# L-D5019-05-02.net
KiCad netlist of a schematic drawn in Altium Designer
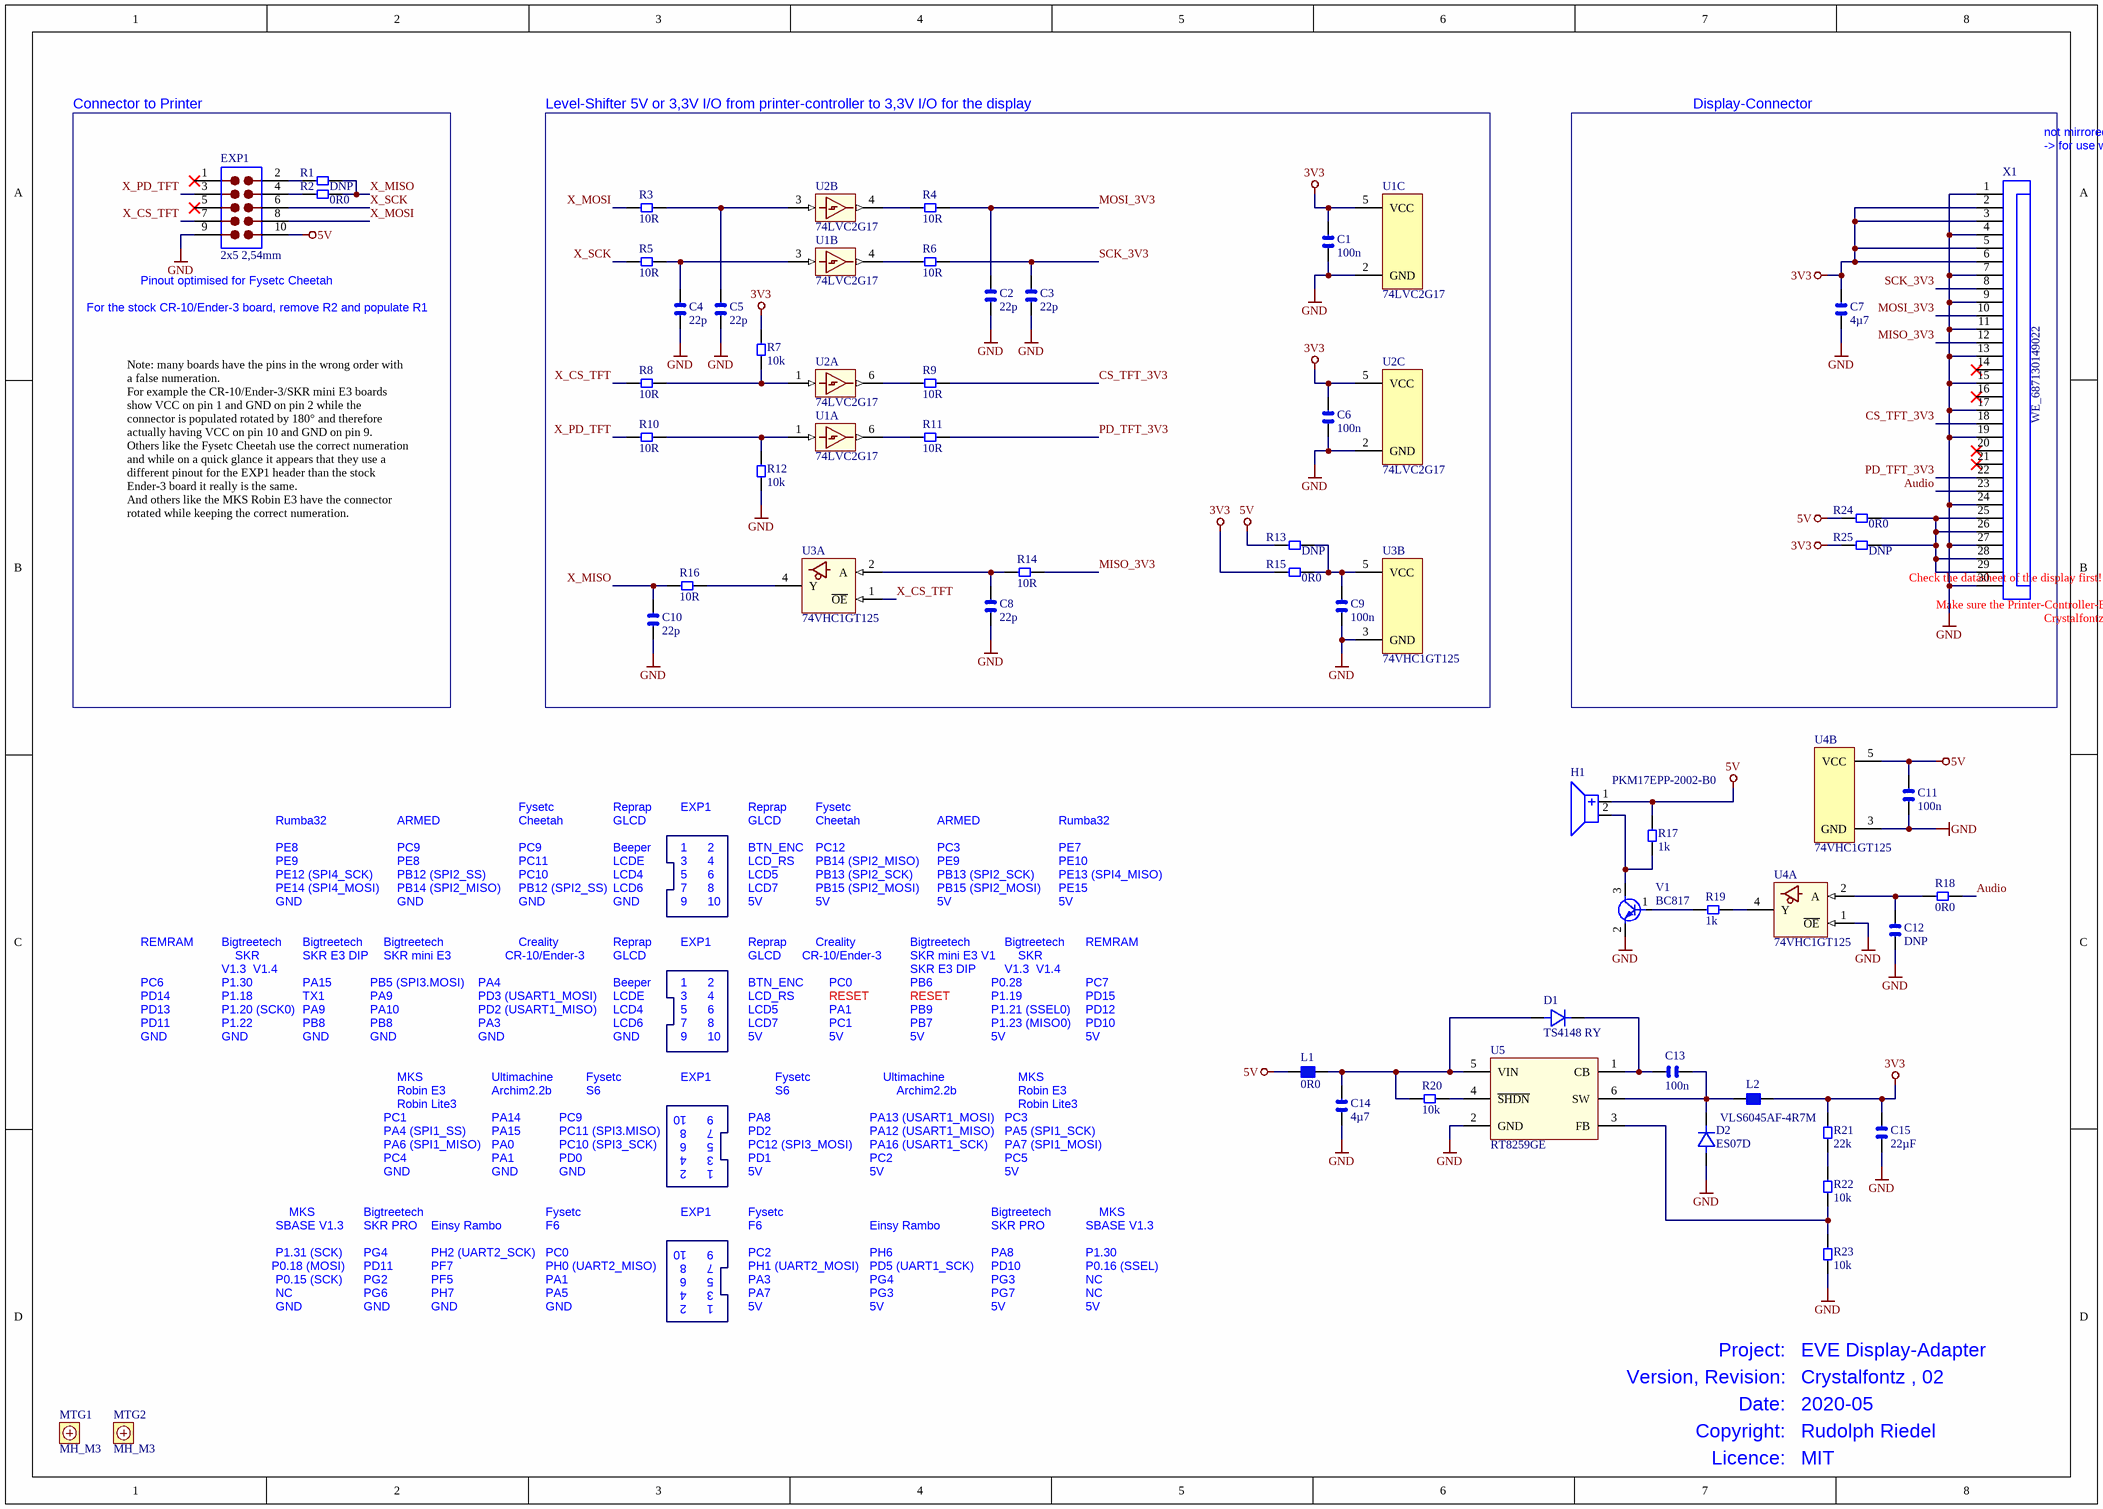
[diagram p0: L-D5019-05-02.SchDoc]

(export (version "E")
  (design (tool "Eeschema 10.0.6"))
  (components
    (comp (ref "C1")
      (value "100n")
      (footprint "CAPC2012X14L")
      (description "0805 Chip Capacitor")
      (fields (field (name "PART NUMBER") "CAPC_0805") (field (name "EDITOR") "rriedel"))
      (libsource (lib "HW-Labor_GF") (part "CAP_2_V2"))
    )
    (comp (ref "C2")
      (value "22p")
      (footprint "CAPC2012X14L")
      (description "0805 Chip Capacitor")
      (fields (field (name "PART NUMBER") "CAPC_0805") (field (name "EDITOR") "rriedel"))
      (libsource (lib "HW-Labor_GF") (part "CAP_2_V2"))
    )
    (comp (ref "C3")
      (value "22p")
      (footprint "CAPC2012X14L")
      (description "0805 Chip Capacitor")
      (fields (field (name "PART NUMBER") "CAPC_0805") (field (name "EDITOR") "rriedel"))
      (libsource (lib "HW-Labor_GF") (part "CAP_2_V2"))
    )
    (comp (ref "C4")
      (value "22p")
      (footprint "CAPC2012X14L")
      (description "0805 Chip Capacitor")
      (fields (field (name "PART NUMBER") "CAPC_0805") (field (name "EDITOR") "rriedel"))
      (libsource (lib "HW-Labor_GF") (part "CAP_2_V2"))
    )
    (comp (ref "C5")
      (value "22p")
      (footprint "CAPC2012X14L")
      (description "0805 Chip Capacitor")
      (fields (field (name "PART NUMBER") "CAPC_0805") (field (name "EDITOR") "rriedel"))
      (libsource (lib "HW-Labor_GF") (part "CAP_2_V2"))
    )
    (comp (ref "C6")
      (value "100n")
      (footprint "CAPC2012X14L")
      (description "0805 Chip Capacitor")
      (fields (field (name "PART NUMBER") "CAPC_0805") (field (name "EDITOR") "rriedel"))
      (libsource (lib "HW-Labor_GF") (part "CAP_2_V2"))
    )
    (comp (ref "C7")
      (value "4µ7")
      (footprint "CAPC2012X14L")
      (description "0805 Chip Capacitor")
      (fields (field (name "PART NUMBER") "CAPC_0805") (field (name "EDITOR") "rriedel"))
      (libsource (lib "HW-Labor_GF") (part "CAP_2_V2"))
    )
    (comp (ref "C8")
      (value "22p")
      (footprint "CAPC2012X14L")
      (description "0805 Chip Capacitor")
      (fields (field (name "PART NUMBER") "CAPC_0805") (field (name "EDITOR") "rriedel"))
      (libsource (lib "HW-Labor_GF") (part "CAP_2_V2"))
    )
    (comp (ref "C9")
      (value "100n")
      (footprint "CAPC2012X14L")
      (description "0805 Chip Capacitor")
      (fields (field (name "PART NUMBER") "CAPC_0805") (field (name "EDITOR") "rriedel"))
      (libsource (lib "HW-Labor_GF") (part "CAP_2_V2"))
    )
    (comp (ref "C10")
      (value "22p")
      (footprint "CAPC2012X14L")
      (description "0805 Chip Capacitor")
      (fields (field (name "PART NUMBER") "CAPC_0805") (field (name "EDITOR") "rriedel"))
      (libsource (lib "HW-Labor_GF") (part "CAP_2_V2"))
    )
    (comp (ref "C11")
      (value "100n")
      (footprint "CAPC2012X14L")
      (description "0805 Chip Capacitor")
      (fields (field (name "PART NUMBER") "CAPC_0805") (field (name "EDITOR") "rriedel"))
      (libsource (lib "HW-Labor_GF") (part "CAP_2_V2"))
    )
    (comp (ref "C12")
      (value "DNP")
      (footprint "CAPC2012X14L")
      (description "0805 Chip Capacitor")
      (fields (field (name "PART NUMBER") "CAPC_0805") (field (name "EDITOR") "rriedel"))
      (libsource (lib "HW-Labor_GF") (part "CAP_2_V2"))
    )
    (comp (ref "C13")
      (value "100n")
      (footprint "CAPC2012X14L")
      (description "0805 Chip Capacitor")
      (fields (field (name "PART NUMBER") "CAPC_0805") (field (name "EDITOR") "rriedel"))
      (libsource (lib "HW-Labor_GF") (part "CAP_2_V2"))
    )
    (comp (ref "C14")
      (value "4µ7")
      (footprint "CAPC2012X14L")
      (description "0805 Chip Capacitor")
      (fields (field (name "PART NUMBER") "CAPC_0805") (field (name "EDITOR") "rriedel"))
      (libsource (lib "HW-Labor_GF") (part "CAP_2_V2"))
    )
    (comp (ref "C15")
      (value "22µF")
      (footprint "CAPC3216X19N")
      (description "1206 Chip Capacitor")
      (fields (field (name "PART NUMBER") "CAPC_1206") (field (name "EDITOR") "rriedel"))
      (libsource (lib "HW-Labor_GF") (part "CAP_2_V2"))
    )
    (comp (ref "D1")
      (value "TS4148 RY")
      (footprint "DIOC2012X10N")
      (description "Small Signal Diode IF 0.3A, VR 75V, 0805")
      (fields
        (field (name "PART NUMBER") "TSC_TS4148 RY")
        (field (name "MANUFACTURER") "TSC")
        (field (name "EDITOR") "rriedel")
      )
      (libsource (lib "HW-Labor_GF") (part "Diode_A2_K1"))
    )
    (comp (ref "D2")
      (value "ES07D")
      (footprint "DIOM2818X11N")
      (description "Ultrafast Rectifier Surface Mount,  IF 0.5A, VR 100V, DO-219AB, AEC-Q101")
      (fields (field (name "MANUFACTURER") "Vishay") (field (name "EDITOR") "rriedel"))
      (libsource (lib "HW-Labor_GF") (part "Diode_A2_K1"))
    )
    (comp (ref "EXP1")
      (value "2x5 2,54mm")
      (footprint "PINH_2x5_2_54mm_shroud")
      (description "Pin-Header 2,54 mm 2x5pins, shrouded")
      (fields (field (name "PART NUMBER") "PINH_2x5_2_54") (field (name "EDITOR") "rriedel"))
      (libsource (lib "HW-Labor_GF") (part "CONM_2x5_V2"))
    )
    (comp (ref "H1")
      (value "PKM17EPP-2002-B0")
      (footprint "Speaker_17mm")
      (description "Speaker, Piezo, THT, dia 17mm,  height 8.6 mm")
      (fields
        (field (name "MANUFACTURER") "Murata")
        (field (name "DISTRIBUTOR_1_PART_NUMBER") "490-4688-ND")
        (field (name "EDITOR") "rriedel")
      )
      (libsource (lib "HW-Labor_GF") (part "Speaker"))
    )
    (comp (ref "L1")
      (value "0R0")
      (footprint "INDC2012X10L")
      (description "0805 Chip Inductor")
      (fields (field (name "PART NUMBER") "INDC_0805") (field (name "EDITOR") "rriedel"))
      (libsource (lib "HW-Labor_GF") (part "IND_2_V1"))
    )
    (comp (ref "L2")
      (value "VLS6045AF-4R7M")
      (footprint "PowerInductor_6x6")
      (description "4,7µH, shielded, 4,7A, 26mR")
      (fields
        (field (name "MANUFACTURER") "TDK")
        (field (name "DISTRIBUTOR_1_PART_NUMBER") "445-180835-1-ND")
        (field (name "EDITOR") "rriedel")
      )
      (libsource (lib "HW-Labor_GF") (part "IND_2_V1"))
    )
    (comp (ref "MTG1")
      (value "MH_M3")
      (footprint "HOLE_3_2MM")
      (description "Mounting-Hole for M3 screws")
      (fields (field (name "EDITOR") "rriedel"))
      (libsource (lib "HW-Labor_GF") (part "MTG_V1"))
    )
    (comp (ref "MTG2")
      (value "MH_M3")
      (footprint "HOLE_3_2MM")
      (description "Mounting-Hole for M3 screws")
      (fields (field (name "EDITOR") "rriedel"))
      (libsource (lib "HW-Labor_GF") (part "MTG_V1"))
    )
    (comp (ref "R1")
      (value "DNP")
      (footprint "RESC2012X06L")
      (description "0805 Chip Resistor")
      (fields (field (name "PART NUMBER") "RESC_0805") (field (name "EDITOR") "rriedel"))
      (libsource (lib "HW-Labor_GF") (part "RES_2_V2"))
    )
    (comp (ref "R2")
      (value "0R0")
      (footprint "RESC2012X06L")
      (description "0805 Chip Resistor")
      (fields (field (name "PART NUMBER") "RESC_0805") (field (name "EDITOR") "rriedel"))
      (libsource (lib "HW-Labor_GF") (part "RES_2_V2"))
    )
    (comp (ref "R3")
      (value "10R")
      (footprint "RESC2012X06L")
      (description "0805 Chip Resistor")
      (fields (field (name "PART NUMBER") "RESC_0805") (field (name "EDITOR") "rriedel"))
      (libsource (lib "HW-Labor_GF") (part "RES_2_V2"))
    )
    (comp (ref "R4")
      (value "10R")
      (footprint "RESC2012X06L")
      (description "0805 Chip Resistor")
      (fields (field (name "PART NUMBER") "RESC_0805") (field (name "EDITOR") "rriedel"))
      (libsource (lib "HW-Labor_GF") (part "RES_2_V2"))
    )
    (comp (ref "R5")
      (value "10R")
      (footprint "RESC2012X06L")
      (description "0805 Chip Resistor")
      (fields (field (name "PART NUMBER") "RESC_0805") (field (name "EDITOR") "rriedel"))
      (libsource (lib "HW-Labor_GF") (part "RES_2_V2"))
    )
    (comp (ref "R6")
      (value "10R")
      (footprint "RESC2012X06L")
      (description "0805 Chip Resistor")
      (fields (field (name "PART NUMBER") "RESC_0805") (field (name "EDITOR") "rriedel"))
      (libsource (lib "HW-Labor_GF") (part "RES_2_V2"))
    )
    (comp (ref "R7")
      (value "10k")
      (footprint "RESC2012X06L")
      (description "0805 Chip Resistor")
      (fields (field (name "PART NUMBER") "RESC_0805") (field (name "EDITOR") "rriedel"))
      (libsource (lib "HW-Labor_GF") (part "RES_2_V2"))
    )
    (comp (ref "R8")
      (value "10R")
      (footprint "RESC2012X06L")
      (description "0805 Chip Resistor")
      (fields (field (name "PART NUMBER") "RESC_0805") (field (name "EDITOR") "rriedel"))
      (libsource (lib "HW-Labor_GF") (part "RES_2_V2"))
    )
    (comp (ref "R9")
      (value "10R")
      (footprint "RESC2012X06L")
      (description "0805 Chip Resistor")
      (fields (field (name "PART NUMBER") "RESC_0805") (field (name "EDITOR") "rriedel"))
      (libsource (lib "HW-Labor_GF") (part "RES_2_V2"))
    )
    (comp (ref "R10")
      (value "10R")
      (footprint "RESC2012X06L")
      (description "0805 Chip Resistor")
      (fields (field (name "PART NUMBER") "RESC_0805") (field (name "EDITOR") "rriedel"))
      (libsource (lib "HW-Labor_GF") (part "RES_2_V2"))
    )
    (comp (ref "R11")
      (value "10R")
      (footprint "RESC2012X06L")
      (description "0805 Chip Resistor")
      (fields (field (name "PART NUMBER") "RESC_0805") (field (name "EDITOR") "rriedel"))
      (libsource (lib "HW-Labor_GF") (part "RES_2_V2"))
    )
    (comp (ref "R12")
      (value "10k")
      (footprint "RESC2012X06L")
      (description "0805 Chip Resistor")
      (fields (field (name "PART NUMBER") "RESC_0805") (field (name "EDITOR") "rriedel"))
      (libsource (lib "HW-Labor_GF") (part "RES_2_V2"))
    )
    (comp (ref "R13")
      (value "DNP")
      (footprint "RESC2012X06L")
      (description "0805 Chip Resistor")
      (fields (field (name "PART NUMBER") "RESC_0805") (field (name "EDITOR") "rriedel"))
      (libsource (lib "HW-Labor_GF") (part "RES_2_V2"))
    )
    (comp (ref "R14")
      (value "10R")
      (footprint "RESC2012X06L")
      (description "0805 Chip Resistor")
      (fields (field (name "PART NUMBER") "RESC_0805") (field (name "EDITOR") "rriedel"))
      (libsource (lib "HW-Labor_GF") (part "RES_2_V2"))
    )
    (comp (ref "R15")
      (value "0R0")
      (footprint "RESC2012X06L")
      (description "0805 Chip Resistor")
      (fields (field (name "PART NUMBER") "RESC_0805") (field (name "EDITOR") "rriedel"))
      (libsource (lib "HW-Labor_GF") (part "RES_2_V2"))
    )
    (comp (ref "R16")
      (value "10R")
      (footprint "RESC2012X06L")
      (description "0805 Chip Resistor")
      (fields (field (name "PART NUMBER") "RESC_0805") (field (name "EDITOR") "rriedel"))
      (libsource (lib "HW-Labor_GF") (part "RES_2_V2"))
    )
    (comp (ref "R17")
      (value "1k")
      (footprint "RESC2012X06L")
      (description "0805 Chip Resistor")
      (fields (field (name "PART NUMBER") "RESC_0805") (field (name "EDITOR") "rriedel"))
      (libsource (lib "HW-Labor_GF") (part "RES_2_V2"))
    )
    (comp (ref "R18")
      (value "0R0")
      (footprint "RESC2012X06L")
      (description "0805 Chip Resistor")
      (fields (field (name "PART NUMBER") "RESC_0805") (field (name "EDITOR") "rriedel"))
      (libsource (lib "HW-Labor_GF") (part "RES_2_V2"))
    )
    (comp (ref "R19")
      (value "1k")
      (footprint "RESC2012X06L")
      (description "0805 Chip Resistor")
      (fields (field (name "PART NUMBER") "RESC_0805") (field (name "EDITOR") "rriedel"))
      (libsource (lib "HW-Labor_GF") (part "RES_2_V2"))
    )
    (comp (ref "R20")
      (value "10k")
      (footprint "RESC2012X06L")
      (description "0805 Chip Resistor")
      (fields (field (name "PART NUMBER") "RESC_0805") (field (name "EDITOR") "rriedel"))
      (libsource (lib "HW-Labor_GF") (part "RES_2_V2"))
    )
    (comp (ref "R21")
      (value "22k")
      (footprint "RESC2012X06L")
      (description "0805 Chip Resistor")
      (fields (field (name "PART NUMBER") "RESC_0805") (field (name "EDITOR") "rriedel"))
      (libsource (lib "HW-Labor_GF") (part "RES_2_V2"))
    )
    (comp (ref "R22")
      (value "10k")
      (footprint "RESC2012X06L")
      (description "0805 Chip Resistor")
      (fields (field (name "PART NUMBER") "RESC_0805") (field (name "EDITOR") "rriedel"))
      (libsource (lib "HW-Labor_GF") (part "RES_2_V2"))
    )
    (comp (ref "R23")
      (value "10k")
      (footprint "RESC2012X06L")
      (description "0805 Chip Resistor")
      (fields (field (name "PART NUMBER") "RESC_0805") (field (name "EDITOR") "rriedel"))
      (libsource (lib "HW-Labor_GF") (part "RES_2_V2"))
    )
    (comp (ref "R24")
      (value "0R0")
      (footprint "RESC2012X06L")
      (description "0805 Chip Resistor")
      (fields (field (name "PART NUMBER") "RESC_0805") (field (name "EDITOR") "rriedel"))
      (libsource (lib "HW-Labor_GF") (part "RES_2_V2"))
    )
    (comp (ref "R25")
      (value "DNP")
      (footprint "RESC2012X06L")
      (description "0805 Chip Resistor")
      (fields (field (name "PART NUMBER") "RESC_0805") (field (name "EDITOR") "rriedel"))
      (libsource (lib "HW-Labor_GF") (part "RES_2_V2"))
    )
    (comp (ref "U1")
      (value "74LVC2G17")
      (footprint "SOT95P280X110-6N")
      (description "Dual Schmitt-Trigger Buffer with 5.5V tolerant inputs")
      (fields
        (field (name "MANUFACTURER") "TI")
        (field (name "DISTRIBUTOR_1_PART_NUMBER") "296-SN74LVC2G17DBVRCT-ND‎")
        (field (name "EDITOR") "rriedel")
      )
      (libsource (lib "HW-Labor_GF") (part "74LVC2G17"))
    )
    (comp (ref "U2")
      (value "74LVC2G17")
      (footprint "SOT95P280X110-6N")
      (description "Dual Schmitt-Trigger Buffer with 5.5V tolerant inputs")
      (fields
        (field (name "MANUFACTURER") "TI")
        (field (name "DISTRIBUTOR_1_PART_NUMBER") "296-SN74LVC2G17DBVRCT-ND‎")
        (field (name "EDITOR") "rriedel")
      )
      (libsource (lib "HW-Labor_GF") (part "74LVC2G17"))
    )
    (comp (ref "U3")
      (value "74VHC1GT125")
      (footprint "SOT95P280X110-5N")
      (description "1x Buffer with OE; 3-state,Level Shifter 3,3V to 5V and 5V to 3.3V")
      (fields
        (field (name "MANUFACTURER") "ON Semiconductor")
        (field (name "DISTRIBUTOR_1_PART_NUMBER") "1703291")
        (field (name "EDITOR") "rriedel")
      )
      (libsource (lib "") (part "74LVC1G125G_1"))
    )
    (comp (ref "U4")
      (value "74VHC1GT125")
      (footprint "SOT95P280X110-5N")
      (description "1x Buffer with OE; 3-state,Level Shifter 3,3V to 5V and 5V to 3.3V")
      (fields
        (field (name "MANUFACTURER") "ON Semiconductor")
        (field (name "DISTRIBUTOR_1_PART_NUMBER") "1703291")
        (field (name "EDITOR") "rriedel")
      )
      (libsource (lib "HW-Labor_GF") (part "74LVC1G125G"))
    )
    (comp (ref "U5")
      (value "RT8259GE")
      (footprint "SOT95P280X110-6N")
      (description "Step-Down DC/DC Regulator, 24V, 1.2A, 1,4MHz")
      (fields
        (field (name "MANUFACTURER") "Richtek")
        (field (name "DISTRIBUTOR_1_PART_NUMBER") "1028-1497-1-ND")
        (field (name "EDITOR") "rriedel")
      )
      (libsource (lib "HW-Labor_GF") (part "StepDown_SOT23-6"))
    )
    (comp (ref "V1")
      (value "BC817")
      (footprint "SOT95P280X110-3N")
      (description "NPN Transistor SOT23, 1=B, 2=C, 3=E")
      (fields (field (name "EDITOR") "rriedel"))
      (libsource (lib "HW-Labor_GF") (part "NPN_B1_C2_E3"))
    )
    (comp (ref "X1")
      (value "WE_687130149022")
      (footprint "WE_687130149022")
      (description "30pin WR-FPC 0.50 mm SMT ZIF Horizontal - Bottom Contact")
      (fields
        (field (name "MANUFACTURER") "Wuerth")
        (field (name "DISTRIBUTOR_1_PART_NUMBER") "732-6007-1-ND")
        (field (name "EDITOR") "rriedel")
      )
      (libsource (lib "HW-Labor_GF") (part "FPC_30"))
    )
  )
  (nets
    (net (code "1") (name "/Audio") (class "Default")
      (node (ref "R18") (pin "2") (pinfunction "2_2") (pintype "passive"))
      (node (ref "X1") (pin "23") (pinfunction "23_23") (pintype "passive"))
    )
    (net (code "2") (name "/CS_TFT_3V3") (class "Default")
      (node (ref "R9") (pin "2") (pinfunction "2_2") (pintype "passive"))
      (node (ref "X1") (pin "18") (pinfunction "18_18") (pintype "passive"))
    )
    (net (code "3") (name "/MISO_3V3") (class "Default")
      (node (ref "R14") (pin "2") (pinfunction "2_2") (pintype "passive"))
      (node (ref "X1") (pin "12") (pinfunction "12_12") (pintype "passive"))
    )
    (net (code "4") (name "/MOSI_3V3") (class "Default")
      (node (ref "C2") (pin "2") (pinfunction "2_2") (pintype "passive"))
      (node (ref "R4") (pin "2") (pinfunction "2_2") (pintype "passive"))
      (node (ref "X1") (pin "10") (pinfunction "10_10") (pintype "passive"))
    )
    (net (code "5") (name "/PD_TFT_3V3") (class "Default")
      (node (ref "R11") (pin "2") (pinfunction "2_2") (pintype "passive"))
      (node (ref "X1") (pin "22") (pinfunction "22_22") (pintype "passive"))
    )
    (net (code "6") (name "/SCK_3V3") (class "Default")
      (node (ref "C3") (pin "2") (pinfunction "2_2") (pintype "passive"))
      (node (ref "R6") (pin "2") (pinfunction "2_2") (pintype "passive"))
      (node (ref "X1") (pin "8") (pinfunction "8_8") (pintype "passive"))
    )
    (net (code "7") (name "/X_CS_TFT") (class "Default")
      (node (ref "EXP1") (pin "7") (pinfunction "7_7") (pintype "passive"))
      (node (ref "R8") (pin "1") (pinfunction "1_1") (pintype "passive"))
      (node (ref "U3") (pin "1") (pinfunction "~{OE}_1") (pintype "input"))
    )
    (net (code "8") (name "/X_MISO") (class "Default")
      (node (ref "C10") (pin "2") (pinfunction "2_2") (pintype "passive"))
      (node (ref "R1") (pin "2") (pinfunction "2_2") (pintype "passive"))
      (node (ref "R16") (pin "1") (pinfunction "1_1") (pintype "passive"))
      (node (ref "R2") (pin "2") (pinfunction "2_2") (pintype "passive"))
    )
    (net (code "9") (name "/X_MOSI") (class "Default")
      (node (ref "EXP1") (pin "8") (pinfunction "8_8") (pintype "passive"))
      (node (ref "R3") (pin "1") (pinfunction "1_1") (pintype "passive"))
    )
    (net (code "10") (name "/X_PD_TFT") (class "Default")
      (node (ref "EXP1") (pin "3") (pinfunction "3_3") (pintype "passive"))
      (node (ref "R10") (pin "1") (pinfunction "1_1") (pintype "passive"))
    )
    (net (code "11") (name "/X_SCK") (class "Default")
      (node (ref "EXP1") (pin "6") (pinfunction "6_6") (pintype "passive"))
      (node (ref "R5") (pin "1") (pinfunction "1_1") (pintype "passive"))
    )
    (net (code "12") (name "3V3") (class "Default")
      (node (ref "C1") (pin "2") (pinfunction "2_2") (pintype "passive"))
      (node (ref "C15") (pin "2") (pinfunction "2_2") (pintype "passive"))
      (node (ref "C6") (pin "2") (pinfunction "2_2") (pintype "passive"))
      (node (ref "C7") (pin "2") (pinfunction "2_2") (pintype "passive"))
      (node (ref "L2") (pin "2") (pinfunction "2_2") (pintype "passive"))
      (node (ref "R15") (pin "1") (pinfunction "1_1") (pintype "passive"))
      (node (ref "R21") (pin "2") (pinfunction "2_2") (pintype "passive"))
      (node (ref "R25") (pin "1") (pinfunction "1_1") (pintype "passive"))
      (node (ref "R7") (pin "2") (pinfunction "2_2") (pintype "passive"))
      (node (ref "U1") (pin "5") (pinfunction "VCC_5") (pintype "power_in"))
      (node (ref "U2") (pin "5") (pinfunction "VCC_5") (pintype "power_in"))
      (node (ref "X1") (pin "2") (pinfunction "2_2") (pintype "passive"))
      (node (ref "X1") (pin "3") (pinfunction "3_3") (pintype "passive"))
      (node (ref "X1") (pin "5") (pinfunction "5_5") (pintype "passive"))
      (node (ref "X1") (pin "6") (pinfunction "6_6") (pintype "passive"))
    )
    (net (code "13") (name "5V") (class "Default")
      (node (ref "C11") (pin "2") (pinfunction "2_2") (pintype "passive"))
      (node (ref "EXP1") (pin "10") (pinfunction "10_10") (pintype "passive"))
      (node (ref "H1") (pin "1") (pinfunction "1_1") (pintype "passive"))
      (node (ref "L1") (pin "1") (pinfunction "1_1") (pintype "passive"))
      (node (ref "R13") (pin "1") (pinfunction "1_1") (pintype "passive"))
      (node (ref "R17") (pin "2") (pinfunction "2_2") (pintype "passive"))
      (node (ref "R24") (pin "1") (pinfunction "1_1") (pintype "passive"))
      (node (ref "U4") (pin "5") (pinfunction "VCC_5") (pintype "passive"))
    )
    (net (code "14") (name "GND") (class "Default")
      (node (ref "C1") (pin "1") (pinfunction "1_1") (pintype "passive"))
      (node (ref "C10") (pin "1") (pinfunction "1_1") (pintype "passive"))
      (node (ref "C11") (pin "1") (pinfunction "1_1") (pintype "passive"))
      (node (ref "C12") (pin "1") (pinfunction "1_1") (pintype "passive"))
      (node (ref "C14") (pin "1") (pinfunction "1_1") (pintype "passive"))
      (node (ref "C15") (pin "1") (pinfunction "1_1") (pintype "passive"))
      (node (ref "C2") (pin "1") (pinfunction "1_1") (pintype "passive"))
      (node (ref "C3") (pin "1") (pinfunction "1_1") (pintype "passive"))
      (node (ref "C4") (pin "1") (pinfunction "1_1") (pintype "passive"))
      (node (ref "C5") (pin "1") (pinfunction "1_1") (pintype "passive"))
      (node (ref "C6") (pin "1") (pinfunction "1_1") (pintype "passive"))
      (node (ref "C7") (pin "1") (pinfunction "1_1") (pintype "passive"))
      (node (ref "C8") (pin "1") (pinfunction "1_1") (pintype "passive"))
      (node (ref "C9") (pin "1") (pinfunction "1_1") (pintype "passive"))
      (node (ref "D2") (pin "2") (pinfunction "2_2") (pintype "passive"))
      (node (ref "EXP1") (pin "9") (pinfunction "9_9") (pintype "passive"))
      (node (ref "R12") (pin "1") (pinfunction "1_1") (pintype "passive"))
      (node (ref "R23") (pin "1") (pinfunction "1_1") (pintype "passive"))
      (node (ref "U1") (pin "2") (pinfunction "GND_2") (pintype "power_in"))
      (node (ref "U2") (pin "2") (pinfunction "GND_2") (pintype "power_in"))
      (node (ref "U3") (pin "3") (pinfunction "GND_3") (pintype "passive"))
      (node (ref "U4") (pin "1") (pinfunction "~{OE}_1") (pintype "input"))
      (node (ref "U4") (pin "3") (pinfunction "GND_3") (pintype "passive"))
      (node (ref "U5") (pin "2") (pinfunction "GND_2") (pintype "power_in"))
      (node (ref "V1") (pin "2") (pinfunction "2_2") (pintype "passive"))
      (node (ref "X1") (pin "1") (pinfunction "1_1") (pintype "passive"))
      (node (ref "X1") (pin "11") (pinfunction "11_11") (pintype "passive"))
      (node (ref "X1") (pin "13") (pinfunction "13_13") (pintype "passive"))
      (node (ref "X1") (pin "15") (pinfunction "15_15") (pintype "passive"))
      (node (ref "X1") (pin "17") (pinfunction "17_17") (pintype "passive"))
      (node (ref "X1") (pin "19") (pinfunction "19_19") (pintype "passive"))
      (node (ref "X1") (pin "24") (pinfunction "24_24") (pintype "passive"))
      (node (ref "X1") (pin "27") (pinfunction "27_27") (pintype "passive"))
      (node (ref "X1") (pin "30") (pinfunction "30_30") (pintype "passive"))
      (node (ref "X1") (pin "4") (pinfunction "4_4") (pintype "passive"))
      (node (ref "X1") (pin "7") (pinfunction "7_7") (pintype "passive"))
      (node (ref "X1") (pin "9") (pinfunction "9_9") (pintype "passive"))
    )
    (net (code "15") (name "Net-(EXP1-Pad2)") (class "Default")
      (node (ref "EXP1") (pin "2") (pinfunction "2_2") (pintype "passive"))
      (node (ref "R1") (pin "1") (pinfunction "1_1") (pintype "passive"))
    )
    (net (code "16") (name "Net-(EXP1-Pad4)") (class "Default")
      (node (ref "EXP1") (pin "4") (pinfunction "4_4") (pintype "passive"))
      (node (ref "R2") (pin "1") (pinfunction "1_1") (pintype "passive"))
    )
    (net (code "17") (name "Net-(H1-Pad2)") (class "Default")
      (node (ref "H1") (pin "2") (pinfunction "2_2") (pintype "passive"))
      (node (ref "R17") (pin "1") (pinfunction "1_1") (pintype "passive"))
      (node (ref "V1") (pin "3") (pinfunction "3_3") (pintype "passive"))
    )
    (net (code "18") (name "Net-(R19-Pad2)") (class "Default")
      (node (ref "R19") (pin "2") (pinfunction "2_2") (pintype "passive"))
      (node (ref "V1") (pin "1") (pinfunction "1_1") (pintype "passive"))
    )
    (net (code "19") (name "Net-(R21-Pad1)") (class "Default")
      (node (ref "R21") (pin "1") (pinfunction "1_1") (pintype "passive"))
      (node (ref "R22") (pin "2") (pinfunction "2_2") (pintype "passive"))
    )
    (net (code "20") (name "Net-(R24-Pad2)") (class "Default")
      (node (ref "R24") (pin "2") (pinfunction "2_2") (pintype "passive"))
      (node (ref "R25") (pin "2") (pinfunction "2_2") (pintype "passive"))
      (node (ref "X1") (pin "25") (pinfunction "25_25") (pintype "passive"))
      (node (ref "X1") (pin "26") (pinfunction "26_26") (pintype "passive"))
      (node (ref "X1") (pin "28") (pinfunction "28_28") (pintype "passive"))
      (node (ref "X1") (pin "29") (pinfunction "29_29") (pintype "passive"))
    )
    (net (code "21") (name "Net-(U1A-1A)") (class "Default")
      (node (ref "R10") (pin "2") (pinfunction "2_2") (pintype "passive"))
      (node (ref "R12") (pin "2") (pinfunction "2_2") (pintype "passive"))
      (node (ref "U1") (pin "1") (pinfunction "1A_1") (pintype "input"))
    )
    (net (code "22") (name "Net-(U1A-1Y)") (class "Default")
      (node (ref "R11") (pin "1") (pinfunction "1_1") (pintype "passive"))
      (node (ref "U1") (pin "6") (pinfunction "1Y_6") (pintype "output"))
    )
    (net (code "23") (name "Net-(U1B-2A)") (class "Default")
      (node (ref "C4") (pin "2") (pinfunction "2_2") (pintype "passive"))
      (node (ref "R5") (pin "2") (pinfunction "2_2") (pintype "passive"))
      (node (ref "U1") (pin "3") (pinfunction "2A_3") (pintype "input"))
    )
    (net (code "24") (name "Net-(U1B-2Y)") (class "Default")
      (node (ref "R6") (pin "1") (pinfunction "1_1") (pintype "passive"))
      (node (ref "U1") (pin "4") (pinfunction "2Y_4") (pintype "output"))
    )
    (net (code "25") (name "Net-(U2A-1A)") (class "Default")
      (node (ref "R7") (pin "1") (pinfunction "1_1") (pintype "passive"))
      (node (ref "R8") (pin "2") (pinfunction "2_2") (pintype "passive"))
      (node (ref "U2") (pin "1") (pinfunction "1A_1") (pintype "input"))
    )
    (net (code "26") (name "Net-(U2A-1Y)") (class "Default")
      (node (ref "R9") (pin "1") (pinfunction "1_1") (pintype "passive"))
      (node (ref "U2") (pin "6") (pinfunction "1Y_6") (pintype "output"))
    )
    (net (code "27") (name "Net-(U2B-2A)") (class "Default")
      (node (ref "C5") (pin "2") (pinfunction "2_2") (pintype "passive"))
      (node (ref "R3") (pin "2") (pinfunction "2_2") (pintype "passive"))
      (node (ref "U2") (pin "3") (pinfunction "2A_3") (pintype "input"))
    )
    (net (code "28") (name "Net-(U2B-2Y)") (class "Default")
      (node (ref "R4") (pin "1") (pinfunction "1_1") (pintype "passive"))
      (node (ref "U2") (pin "4") (pinfunction "2Y_4") (pintype "output"))
    )
    (net (code "29") (name "Net-(U3A-A)") (class "Default")
      (node (ref "C8") (pin "2") (pinfunction "2_2") (pintype "passive"))
      (node (ref "R14") (pin "1") (pinfunction "1_1") (pintype "passive"))
      (node (ref "U3") (pin "2") (pinfunction "A_2") (pintype "input"))
    )
    (net (code "30") (name "Net-(U3A-Y)") (class "Default")
      (node (ref "R16") (pin "2") (pinfunction "2_2") (pintype "passive"))
      (node (ref "U3") (pin "4") (pinfunction "Y_4") (pintype "tri_state"))
    )
    (net (code "31") (name "Net-(U3B-VCC)") (class "Default")
      (node (ref "C9") (pin "2") (pinfunction "2_2") (pintype "passive"))
      (node (ref "R13") (pin "2") (pinfunction "2_2") (pintype "passive"))
      (node (ref "R15") (pin "2") (pinfunction "2_2") (pintype "passive"))
      (node (ref "U3") (pin "5") (pinfunction "VCC_5") (pintype "passive"))
    )
    (net (code "32") (name "Net-(U4A-A)") (class "Default")
      (node (ref "C12") (pin "2") (pinfunction "2_2") (pintype "passive"))
      (node (ref "R18") (pin "1") (pinfunction "1_1") (pintype "passive"))
      (node (ref "U4") (pin "2") (pinfunction "A_2") (pintype "input"))
    )
    (net (code "33") (name "Net-(U4A-Y)") (class "Default")
      (node (ref "R19") (pin "1") (pinfunction "1_1") (pintype "passive"))
      (node (ref "U4") (pin "4") (pinfunction "Y_4") (pintype "tri_state"))
    )
    (net (code "34") (name "Net-(U5-CB)") (class "Default")
      (node (ref "C13") (pin "1") (pinfunction "1_1") (pintype "passive"))
      (node (ref "D1") (pin "1") (pinfunction "1_1") (pintype "passive"))
      (node (ref "U5") (pin "1") (pinfunction "CB_1") (pintype "passive"))
    )
    (net (code "35") (name "Net-(U5-FB)") (class "Default")
      (node (ref "R22") (pin "1") (pinfunction "1_1") (pintype "passive"))
      (node (ref "R23") (pin "2") (pinfunction "2_2") (pintype "passive"))
      (node (ref "U5") (pin "3") (pinfunction "FB_3") (pintype "passive"))
    )
    (net (code "36") (name "Net-(U5-SW)") (class "Default")
      (node (ref "C13") (pin "2") (pinfunction "2_2") (pintype "passive"))
      (node (ref "D2") (pin "1") (pinfunction "1_1") (pintype "passive"))
      (node (ref "L2") (pin "1") (pinfunction "1_1") (pintype "passive"))
      (node (ref "U5") (pin "6") (pinfunction "SW_6") (pintype "passive"))
    )
    (net (code "37") (name "Net-(U5-VIN)") (class "Default")
      (node (ref "C14") (pin "2") (pinfunction "2_2") (pintype "passive"))
      (node (ref "D1") (pin "2") (pinfunction "2_2") (pintype "passive"))
      (node (ref "L1") (pin "2") (pinfunction "2_2") (pintype "passive"))
      (node (ref "R20") (pin "1") (pinfunction "1_1") (pintype "passive"))
      (node (ref "U5") (pin "5") (pinfunction "VIN_5") (pintype "power_in"))
    )
    (net (code "38") (name "Net-(U5-~{SHDN})") (class "Default")
      (node (ref "R20") (pin "2") (pinfunction "2_2") (pintype "passive"))
      (node (ref "U5") (pin "4") (pinfunction "~{SHDN}_4") (pintype "passive"))
    )
    (net (code "39") (name "unconnected-(EXP1-Pad1)") (class "Default")
      (node (ref "EXP1") (pin "1") (pinfunction "1_1") (pintype "passive+no_connect"))
    )
    (net (code "40") (name "unconnected-(EXP1-Pad5)") (class "Default")
      (node (ref "EXP1") (pin "5") (pinfunction "5_5") (pintype "passive+no_connect"))
    )
    (net (code "41") (name "unconnected-(X1-Pad14)") (class "Default")
      (node (ref "X1") (pin "14") (pinfunction "14_14") (pintype "passive+no_connect"))
    )
    (net (code "42") (name "unconnected-(X1-Pad16)") (class "Default")
      (node (ref "X1") (pin "16") (pinfunction "16_16") (pintype "passive+no_connect"))
    )
    (net (code "43") (name "unconnected-(X1-Pad20)") (class "Default")
      (node (ref "X1") (pin "20") (pinfunction "20_20") (pintype "passive+no_connect"))
    )
    (net (code "44") (name "unconnected-(X1-Pad21)") (class "Default")
      (node (ref "X1") (pin "21") (pinfunction "21_21") (pintype "passive+no_connect"))
    )
  )
)
